# MCU.net
KiCad netlist of a schematic drawn in Altium Designer
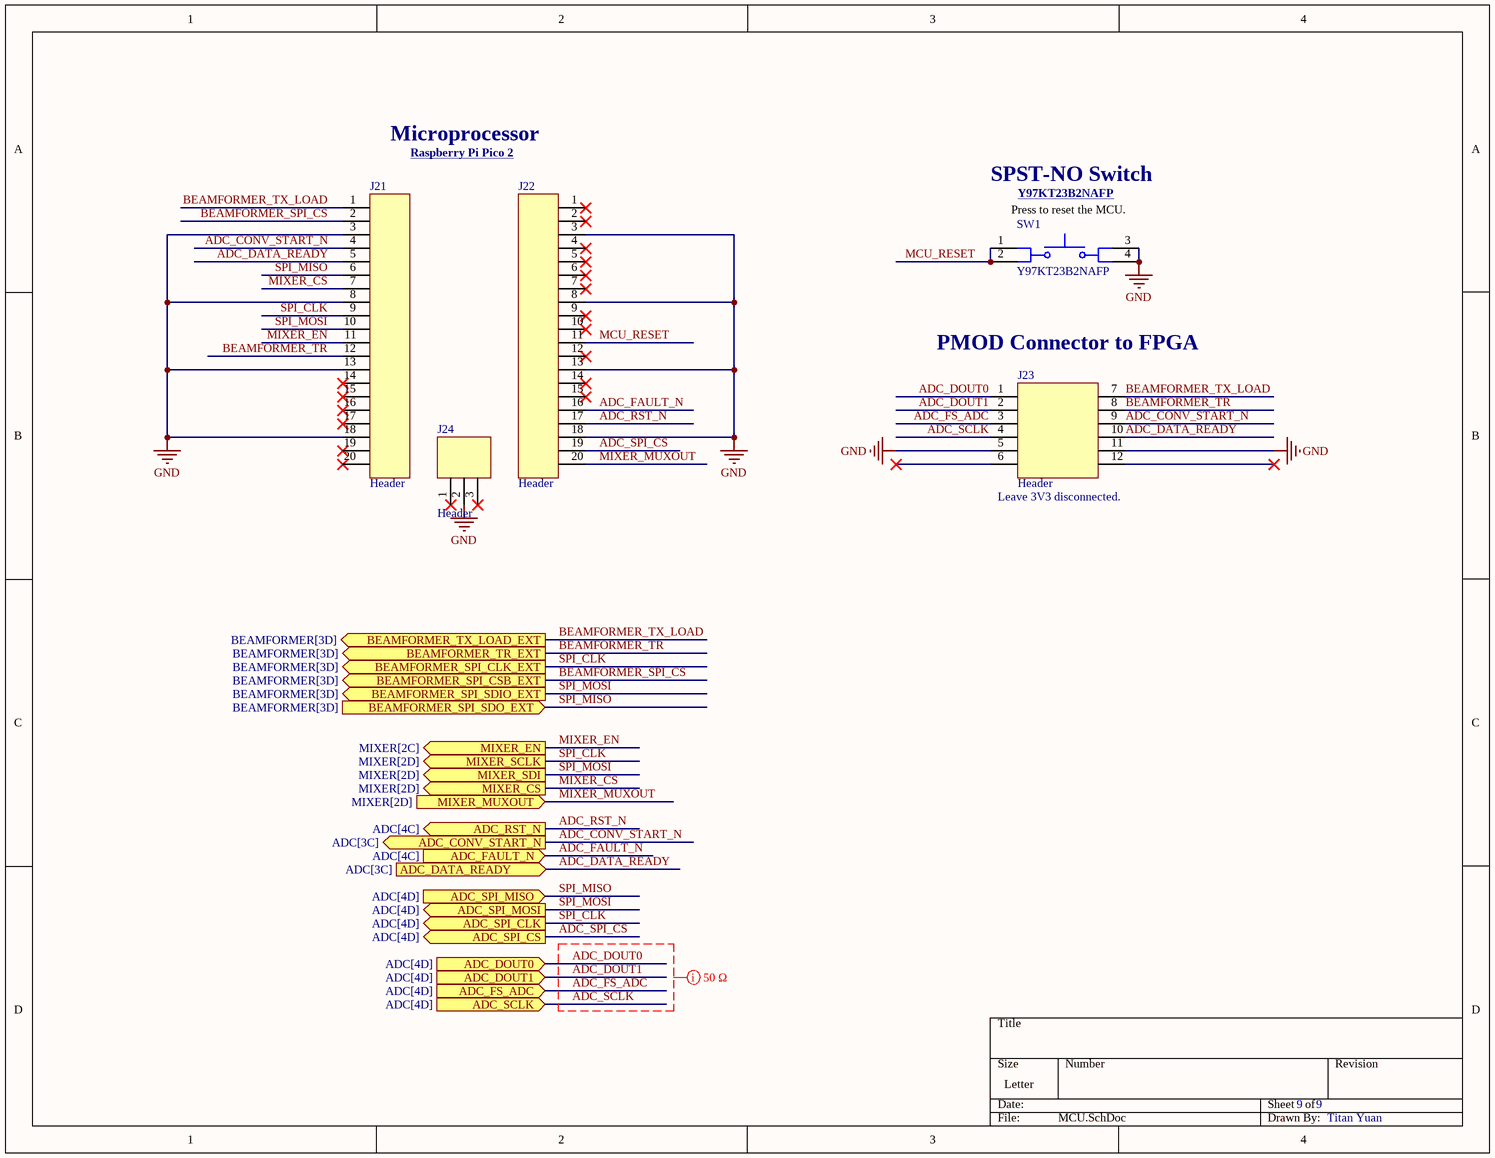
[diagram p0: MCU.SchDoc]

(export (version "E")
  (design (tool "Eeschema 10.0.6"))
  (components
    (comp (ref "J21")
      (value "Header")
      (footprint "CONN_1x20_2.54mm_PinSocket_Vertical")
      (description "WR-PHD 2.54 mm Socket Header; 20 pins")
      (fields
        (field (name "MANUFACTURER") "Wurth Elektronik")
        (field (name "MANUFACTURER PART NUMBER") "61302011821")
      )
      (libsource (lib "") (part "CONN_1x20_2.54mm_PinSocket_Vertical_1"))
    )
    (comp (ref "J22")
      (value "Header")
      (footprint "CONN_1x20_2.54mm_PinSocket_Vertical")
      (description "WR-PHD 2.54 mm Socket Header; 20 pins")
      (fields
        (field (name "MANUFACTURER") "Wurth Elektronik")
        (field (name "MANUFACTURER PART NUMBER") "61302011821")
      )
      (libsource (lib "Titan") (part "CONN_1x20_2.54mm_PinSocket_Vertical"))
    )
    (comp (ref "J23")
      (value "Header")
      (footprint "CONN_2x6_2.54mm_PinHeader_Horizontal")
      (description "Conn Unshrouded Header HDR 12 POS 2.54mm Solder RA Top Entry Thru-Hole Bag")
      (fields
        (field (name "MANUFACTURER") "Adam Tech")
        (field (name "MANUFACTURER PART NUMBER") "PH2RA-12-UA")
      )
      (libsource (lib "Titan") (part "CONN_2x6_2.54mm_PinHeader_Horizontal"))
    )
    (comp (ref "J24")
      (value "Header")
      (footprint "CONN_1x3_2.54mm_PinSocket_Vertical")
      (description "Connector Header Through Hole 3 position 0.100\" (2.54mm)-FAN Control Connector")
      (fields
        (field (name "MANUFACTURER") "Wurth Elektronik")
        (field (name "MANUFACTURER PART NUMBER") "61300311821")
      )
      (libsource (lib "Titan") (part "CONN_1x3_2.54mm_PinSocket_Vertical"))
    )
    (comp (ref "SW1")
      (value "Y97KT23B2NAFP")
      (footprint "PTS647")
      (description "Switch Tactile OFF Mom SPST Round Button Gull Wing 50mA 12VDC 100000Cycles 1.77N Surface Mount T/R")
      (fields (field (name "MANUFACTURER") "C&K"))
      (libsource (lib "Titan") (part "Y97KT23B2NAFP"))
    )
  )
  (nets
    (net (code "1") (name "/ADC_CONV_START_N") (class "Default")
      (node (ref "J21") (pin "4") (pintype "passive"))
      (node (ref "J23") (pin "9") (pintype "passive"))
    )
    (net (code "2") (name "/ADC_DATA_READY") (class "Default")
      (node (ref "J21") (pin "5") (pintype "passive"))
      (node (ref "J23") (pin "10") (pintype "passive"))
    )
    (net (code "3") (name "/ADC_DOUT0") (class "Default") (node (ref "J23") (pin "1") (pintype "passive")))
    (net (code "4") (name "/ADC_DOUT1") (class "Default") (node (ref "J23") (pin "2") (pintype "passive")))
    (net (code "5") (name "/ADC_FAULT_N") (class "Default") (node (ref "J22") (pin "16") (pintype "passive")))
    (net (code "6") (name "/ADC_FS_ADC") (class "Default") (node (ref "J23") (pin "3") (pintype "passive")))
    (net (code "7") (name "/ADC_RST_N") (class "Default") (node (ref "J22") (pin "17") (pintype "passive")))
    (net (code "8") (name "/ADC_SCLK") (class "Default") (node (ref "J23") (pin "4") (pintype "passive")))
    (net (code "9") (name "/ADC_SPI_CS") (class "Default") (node (ref "J22") (pin "19") (pintype "passive")))
    (net (code "10") (name "/BEAMFORMER_SPI_CS") (class "Default")
      (node (ref "J21") (pin "2") (pintype "passive"))
    )
    (net (code "11") (name "/BEAMFORMER_TR") (class "Default")
      (node (ref "J21") (pin "12") (pintype "passive"))
      (node (ref "J23") (pin "8") (pintype "passive"))
    )
    (net (code "12") (name "/BEAMFORMER_TX_LOAD") (class "Default")
      (node (ref "J21") (pin "1") (pintype "passive"))
      (node (ref "J23") (pin "7") (pintype "passive"))
    )
    (net (code "13") (name "/MCU_RESET") (class "Default")
      (node (ref "J22") (pin "11") (pintype "passive"))
      (node (ref "SW1") (pin "1") (pintype "passive"))
      (node (ref "SW1") (pin "2") (pintype "passive"))
    )
    (net (code "14") (name "/MIXER_CS") (class "Default") (node (ref "J21") (pin "7") (pintype "passive")))
    (net (code "15") (name "/MIXER_EN") (class "Default") (node (ref "J21") (pin "11") (pintype "passive")))
    (net (code "16") (name "/MIXER_MUXOUT") (class "Default")
      (node (ref "J22") (pin "20") (pintype "passive"))
    )
    (net (code "17") (name "/SPI_CLK") (class "Default") (node (ref "J21") (pin "9") (pintype "passive")))
    (net (code "18") (name "/SPI_MISO") (class "Default") (node (ref "J21") (pin "6") (pintype "passive")))
    (net (code "19") (name "/SPI_MOSI") (class "Default") (node (ref "J21") (pin "10") (pintype "passive")))
    (net (code "20") (name "GND") (class "Default")
      (node (ref "J21") (pin "13") (pintype "passive"))
      (node (ref "J21") (pin "18") (pintype "passive"))
      (node (ref "J21") (pin "3") (pintype "passive"))
      (node (ref "J21") (pin "8") (pintype "passive"))
      (node (ref "J22") (pin "13") (pintype "passive"))
      (node (ref "J22") (pin "18") (pintype "passive"))
      (node (ref "J22") (pin "3") (pintype "passive"))
      (node (ref "J22") (pin "8") (pintype "passive"))
      (node (ref "J23") (pin "11") (pintype "passive"))
      (node (ref "J23") (pin "5") (pintype "passive"))
      (node (ref "J24") (pin "2") (pintype "passive"))
      (node (ref "SW1") (pin "3") (pintype "passive"))
      (node (ref "SW1") (pin "4") (pintype "passive"))
    )
    (net (code "21") (name "unconnected-(J21-Pad14)") (class "Default")
      (node (ref "J21") (pin "14") (pintype "passive+no_connect"))
    )
    (net (code "22") (name "unconnected-(J21-Pad15)") (class "Default")
      (node (ref "J21") (pin "15") (pintype "passive+no_connect"))
    )
    (net (code "23") (name "unconnected-(J21-Pad16)") (class "Default")
      (node (ref "J21") (pin "16") (pintype "passive+no_connect"))
    )
    (net (code "24") (name "unconnected-(J21-Pad17)") (class "Default")
      (node (ref "J21") (pin "17") (pintype "passive+no_connect"))
    )
    (net (code "25") (name "unconnected-(J21-Pad19)") (class "Default")
      (node (ref "J21") (pin "19") (pintype "passive+no_connect"))
    )
    (net (code "26") (name "unconnected-(J21-Pad20)") (class "Default")
      (node (ref "J21") (pin "20") (pintype "passive+no_connect"))
    )
    (net (code "27") (name "unconnected-(J22-Pad1)") (class "Default")
      (node (ref "J22") (pin "1") (pintype "passive+no_connect"))
    )
    (net (code "28") (name "unconnected-(J22-Pad2)") (class "Default")
      (node (ref "J22") (pin "2") (pintype "passive+no_connect"))
    )
    (net (code "29") (name "unconnected-(J22-Pad4)") (class "Default")
      (node (ref "J22") (pin "4") (pintype "passive+no_connect"))
    )
    (net (code "30") (name "unconnected-(J22-Pad5)") (class "Default")
      (node (ref "J22") (pin "5") (pintype "passive+no_connect"))
    )
    (net (code "31") (name "unconnected-(J22-Pad6)") (class "Default")
      (node (ref "J22") (pin "6") (pintype "passive+no_connect"))
    )
    (net (code "32") (name "unconnected-(J22-Pad7)") (class "Default")
      (node (ref "J22") (pin "7") (pintype "passive+no_connect"))
    )
    (net (code "33") (name "unconnected-(J22-Pad9)") (class "Default")
      (node (ref "J22") (pin "9") (pintype "passive+no_connect"))
    )
    (net (code "34") (name "unconnected-(J22-Pad10)") (class "Default")
      (node (ref "J22") (pin "10") (pintype "passive+no_connect"))
    )
    (net (code "35") (name "unconnected-(J22-Pad12)") (class "Default")
      (node (ref "J22") (pin "12") (pintype "passive+no_connect"))
    )
    (net (code "36") (name "unconnected-(J22-Pad14)") (class "Default")
      (node (ref "J22") (pin "14") (pintype "passive+no_connect"))
    )
    (net (code "37") (name "unconnected-(J22-Pad15)") (class "Default")
      (node (ref "J22") (pin "15") (pintype "passive+no_connect"))
    )
    (net (code "38") (name "unconnected-(J23-Pad6)") (class "Default")
      (node (ref "J23") (pin "6") (pintype "passive+no_connect"))
    )
    (net (code "39") (name "unconnected-(J23-Pad12)") (class "Default")
      (node (ref "J23") (pin "12") (pintype "passive+no_connect"))
    )
    (net (code "40") (name "unconnected-(J24-Pad1)") (class "Default")
      (node (ref "J24") (pin "1") (pintype "passive+no_connect"))
    )
    (net (code "41") (name "unconnected-(J24-Pad3)") (class "Default")
      (node (ref "J24") (pin "3") (pintype "passive+no_connect"))
    )
  )
)
